# NE555.net
KiCad netlist of a schematic drawn in EAGLE
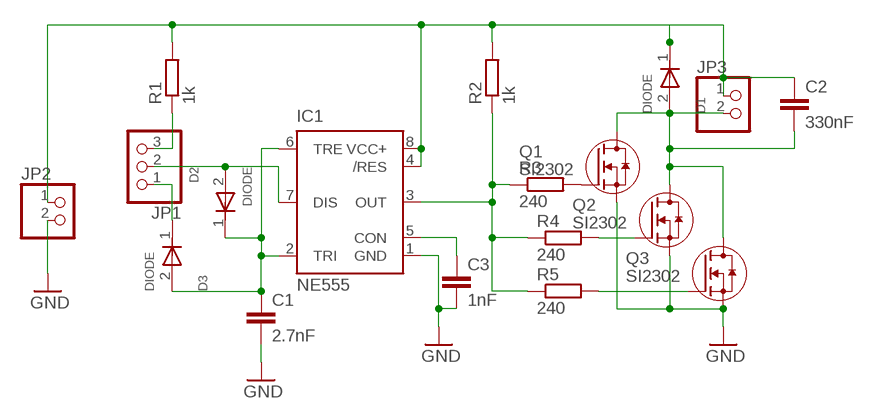
[diagram p0: schematic, sheet 1]

(export (version "E")
  (design (tool "Eeschema 10.0.6"))
  (components
    (comp (ref "C1")
      (value "2.7nF")
      (footprint "eagle-import:C0805")
      (libsource (lib "eagle-import") (part "C-EUC0805"))
    )
    (comp (ref "C2")
      (value "330nF")
      (footprint "eagle-import:C0805")
      (libsource (lib "eagle-import") (part "C-EUC0805"))
    )
    (comp (ref "C3")
      (value "1nF")
      (footprint "eagle-import:C0805")
      (libsource (lib "eagle-import") (part "C-EUC0805"))
    )
    (comp (ref "D1")
      (value "DIODE")
      (footprint "eagle-import:SOD80")
      (libsource (lib "eagle-import") (part "DIODE"))
    )
    (comp (ref "D2")
      (value "DIODE")
      (footprint "eagle-import:SOD80")
      (libsource (lib "eagle-import") (part "DIODE"))
    )
    (comp (ref "D3")
      (value "DIODE")
      (footprint "eagle-import:SOD80")
      (libsource (lib "eagle-import") (part "DIODE"))
    )
    (comp (ref "IC1")
      (value "NE555")
      (footprint "eagle-import:SO08")
      (libsource (lib "eagle-import") (part "NE555"))
    )
    (comp (ref "JP1")
      (value "PINHD-1X3")
      (footprint "eagle-import:1X03")
      (libsource (lib "eagle-import") (part "PINHD-1X3"))
    )
    (comp (ref "JP2")
      (value "PINHD-1X2")
      (footprint "eagle-import:1X02")
      (libsource (lib "eagle-import") (part "PINHD-1X2"))
    )
    (comp (ref "JP3")
      (value "PINHD-1X2")
      (footprint "eagle-import:1X02")
      (libsource (lib "eagle-import") (part "PINHD-1X2"))
    )
    (comp (ref "Q1")
      (value "SI2302")
      (footprint "eagle-import:SOT-23-GSD")
      (libsource (lib "eagle-import") (part "SI2302"))
    )
    (comp (ref "Q2")
      (value "SI2302")
      (footprint "eagle-import:SOT-23-GSD")
      (libsource (lib "eagle-import") (part "SI2302"))
    )
    (comp (ref "Q3")
      (value "SI2302")
      (footprint "eagle-import:SOT-23-GSD")
      (libsource (lib "eagle-import") (part "SI2302"))
    )
    (comp (ref "R1")
      (value "1k")
      (footprint "eagle-import:R0805")
      (libsource (lib "eagle-import") (part "R-EU_R0805"))
    )
    (comp (ref "R2")
      (value "1k")
      (footprint "eagle-import:R0805")
      (libsource (lib "eagle-import") (part "R-EU_R0805"))
    )
    (comp (ref "R3")
      (value "240")
      (footprint "eagle-import:R0805")
      (libsource (lib "eagle-import") (part "R-EU_R0805"))
    )
    (comp (ref "R4")
      (value "240")
      (footprint "eagle-import:R0805")
      (libsource (lib "eagle-import") (part "R-EU_R0805"))
    )
    (comp (ref "R5")
      (value "240")
      (footprint "eagle-import:R0805")
      (libsource (lib "eagle-import") (part "R-EU_R0805"))
    )
  )
  (nets
    (net (code "1") (name "GND") (class "Default")
      (node (ref "C1") (pin "2") (pinfunction "2_2") (pintype "passive"))
      (node (ref "C3") (pin "2") (pinfunction "2_2") (pintype "passive"))
      (node (ref "IC1") (pin "1") (pinfunction "GND_1") (pintype "power_in"))
      (node (ref "JP2") (pin "2") (pinfunction "2_2") (pintype "passive"))
      (node (ref "Q1") (pin "S") (pinfunction "S_S") (pintype "passive"))
      (node (ref "Q2") (pin "S") (pinfunction "S_S") (pintype "passive"))
      (node (ref "Q3") (pin "S") (pinfunction "S_S") (pintype "passive"))
    )
    (net (code "2") (name "Net-(D1-ANOD)") (class "Default")
      (node (ref "C2") (pin "2") (pinfunction "2_2") (pintype "passive"))
      (node (ref "D1") (pin "2") (pinfunction "ANOD_2") (pintype "power_in"))
      (node (ref "JP3") (pin "2") (pinfunction "2_2") (pintype "passive"))
      (node (ref "Q1") (pin "D") (pinfunction "D_D") (pintype "passive"))
      (node (ref "Q2") (pin "D") (pinfunction "D_D") (pintype "passive"))
      (node (ref "Q3") (pin "D") (pinfunction "D_D") (pintype "passive"))
    )
    (net (code "3") (name "Net-(D1-KATOD)") (class "Default")
      (node (ref "C2") (pin "1") (pinfunction "1_1") (pintype "passive"))
      (node (ref "D1") (pin "1") (pinfunction "KATOD_1") (pintype "power_in"))
      (node (ref "IC1") (pin "4") (pinfunction "/RES_4") (pintype "input"))
      (node (ref "IC1") (pin "8") (pinfunction "VCC+_8") (pintype "power_in"))
      (node (ref "JP2") (pin "1") (pinfunction "1_1") (pintype "passive"))
      (node (ref "JP3") (pin "1") (pinfunction "1_1") (pintype "passive"))
      (node (ref "R1") (pin "2") (pinfunction "2_2") (pintype "passive"))
      (node (ref "R2") (pin "2") (pinfunction "2_2") (pintype "passive"))
    )
    (net (code "4") (name "Net-(D2-ANOD)") (class "Default")
      (node (ref "D2") (pin "2") (pinfunction "ANOD_2") (pintype "power_in"))
      (node (ref "IC1") (pin "7") (pinfunction "DIS_7") (pintype "input"))
      (node (ref "JP1") (pin "2") (pinfunction "2_2") (pintype "passive"))
    )
    (net (code "5") (name "Net-(D2-KATOD)") (class "Default")
      (node (ref "C1") (pin "1") (pinfunction "1_1") (pintype "passive"))
      (node (ref "D2") (pin "1") (pinfunction "KATOD_1") (pintype "power_in"))
      (node (ref "D3") (pin "2") (pinfunction "ANOD_2") (pintype "power_in"))
      (node (ref "IC1") (pin "2") (pinfunction "TRI_2") (pintype "input"))
      (node (ref "IC1") (pin "6") (pinfunction "TRE_6") (pintype "input"))
    )
    (net (code "6") (name "Net-(D3-KATOD)") (class "Default")
      (node (ref "D3") (pin "1") (pinfunction "KATOD_1") (pintype "power_in"))
      (node (ref "JP1") (pin "1") (pinfunction "1_1") (pintype "passive"))
    )
    (net (code "7") (name "Net-(IC1-CON)") (class "Default")
      (node (ref "C3") (pin "1") (pinfunction "1_1") (pintype "passive"))
      (node (ref "IC1") (pin "5") (pinfunction "CON_5") (pintype "input"))
    )
    (net (code "8") (name "Net-(IC1-OUT)") (class "Default")
      (node (ref "IC1") (pin "3") (pinfunction "OUT_3") (pintype "output"))
      (node (ref "R2") (pin "1") (pinfunction "1_1") (pintype "passive"))
      (node (ref "R3") (pin "1") (pinfunction "1_1") (pintype "passive"))
      (node (ref "R4") (pin "1") (pinfunction "1_1") (pintype "passive"))
      (node (ref "R5") (pin "1") (pinfunction "1_1") (pintype "passive"))
    )
    (net (code "9") (name "Net-(JP1-Pad3)") (class "Default")
      (node (ref "JP1") (pin "3") (pinfunction "3_3") (pintype "passive"))
      (node (ref "R1") (pin "1") (pinfunction "1_1") (pintype "passive"))
    )
    (net (code "10") (name "Net-(Q1-PadG)") (class "Default")
      (node (ref "Q1") (pin "G") (pinfunction "G_G") (pintype "passive"))
      (node (ref "R3") (pin "2") (pinfunction "2_2") (pintype "passive"))
    )
    (net (code "11") (name "Net-(Q2-PadG)") (class "Default")
      (node (ref "Q2") (pin "G") (pinfunction "G_G") (pintype "passive"))
      (node (ref "R4") (pin "2") (pinfunction "2_2") (pintype "passive"))
    )
    (net (code "12") (name "Net-(Q3-PadG)") (class "Default")
      (node (ref "Q3") (pin "G") (pinfunction "G_G") (pintype "passive"))
      (node (ref "R5") (pin "2") (pinfunction "2_2") (pintype "passive"))
    )
  )
)
